# LORA.net
KiCad netlist of a schematic drawn in Altium Designer
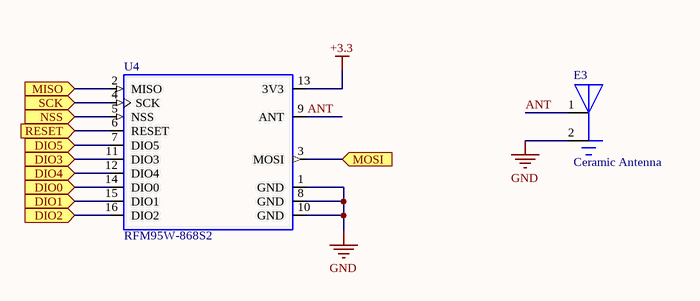
[diagram p0: LORA.SchDoc]

(export (version "E")
  (design (tool "Eeschema 10.0.6"))
  (components
    (comp (ref "E3")
      (value "Ceramic Antenna")
      (footprint "Ceramic_915M")
      (libsource (lib "Antenna") (part "Ceramic Antenna"))
    )
    (comp (ref "U4")
      (value "RFM95W-868S2")
      (footprint "XCVR_RFM95W-868S2")
      (description "General ISM < 1GHz LoRa Transceiver Module 868MHz Antenna Not Included Surface Mount")
      (fields (field (name "MF") "RF"))
      (libsource (lib "RF Module") (part "RFM95W-868S2"))
    )
  )
  (nets
    (net (code "1") (name "+3.3") (class "Default")
      (node (ref "U4") (pin "13") (pinfunction "3V3_13") (pintype "power_in"))
    )
    (net (code "2") (name "/ANT") (class "Default")
      (node (ref "E3") (pin "1") (pinfunction "1_1") (pintype "passive"))
      (node (ref "U4") (pin "9") (pinfunction "ANT_9") (pintype "passive"))
    )
    (net (code "3") (name "/DIO0") (class "Default")
      (node (ref "U4") (pin "14") (pinfunction "DIO0_14") (pintype "bidirectional"))
    )
    (net (code "4") (name "/DIO1") (class "Default")
      (node (ref "U4") (pin "15") (pinfunction "DIO1_15") (pintype "bidirectional"))
    )
    (net (code "5") (name "/DIO2") (class "Default")
      (node (ref "U4") (pin "16") (pinfunction "DIO2_16") (pintype "bidirectional"))
    )
    (net (code "6") (name "/DIO3") (class "Default")
      (node (ref "U4") (pin "11") (pinfunction "DIO3_11") (pintype "bidirectional"))
    )
    (net (code "7") (name "/DIO4") (class "Default")
      (node (ref "U4") (pin "12") (pinfunction "DIO4_12") (pintype "bidirectional"))
    )
    (net (code "8") (name "/DIO5") (class "Default")
      (node (ref "U4") (pin "7") (pinfunction "DIO5_7") (pintype "bidirectional"))
    )
    (net (code "9") (name "/MISO") (class "Default")
      (node (ref "U4") (pin "2") (pinfunction "MISO_2") (pintype "input"))
    )
    (net (code "10") (name "/MOSI") (class "Default")
      (node (ref "U4") (pin "3") (pinfunction "MOSI_3") (pintype "output"))
    )
    (net (code "11") (name "/NSS") (class "Default")
      (node (ref "U4") (pin "5") (pinfunction "NSS_5") (pintype "input"))
    )
    (net (code "12") (name "/RESET") (class "Default")
      (node (ref "U4") (pin "6") (pinfunction "RESET_6") (pintype "bidirectional"))
    )
    (net (code "13") (name "/SCK") (class "Default")
      (node (ref "U4") (pin "4") (pinfunction "SCK_4") (pintype "input"))
    )
    (net (code "14") (name "GND") (class "Default")
      (node (ref "E3") (pin "2") (pinfunction "2_2") (pintype "passive"))
      (node (ref "U4") (pin "1") (pinfunction "GND_1") (pintype "power_in"))
      (node (ref "U4") (pin "10") (pinfunction "GND_10") (pintype "power_in"))
      (node (ref "U4") (pin "8") (pinfunction "GND_8") (pintype "power_in"))
    )
  )
)
